# Memory.net
KiCad netlist of a schematic drawn in Altium Designer
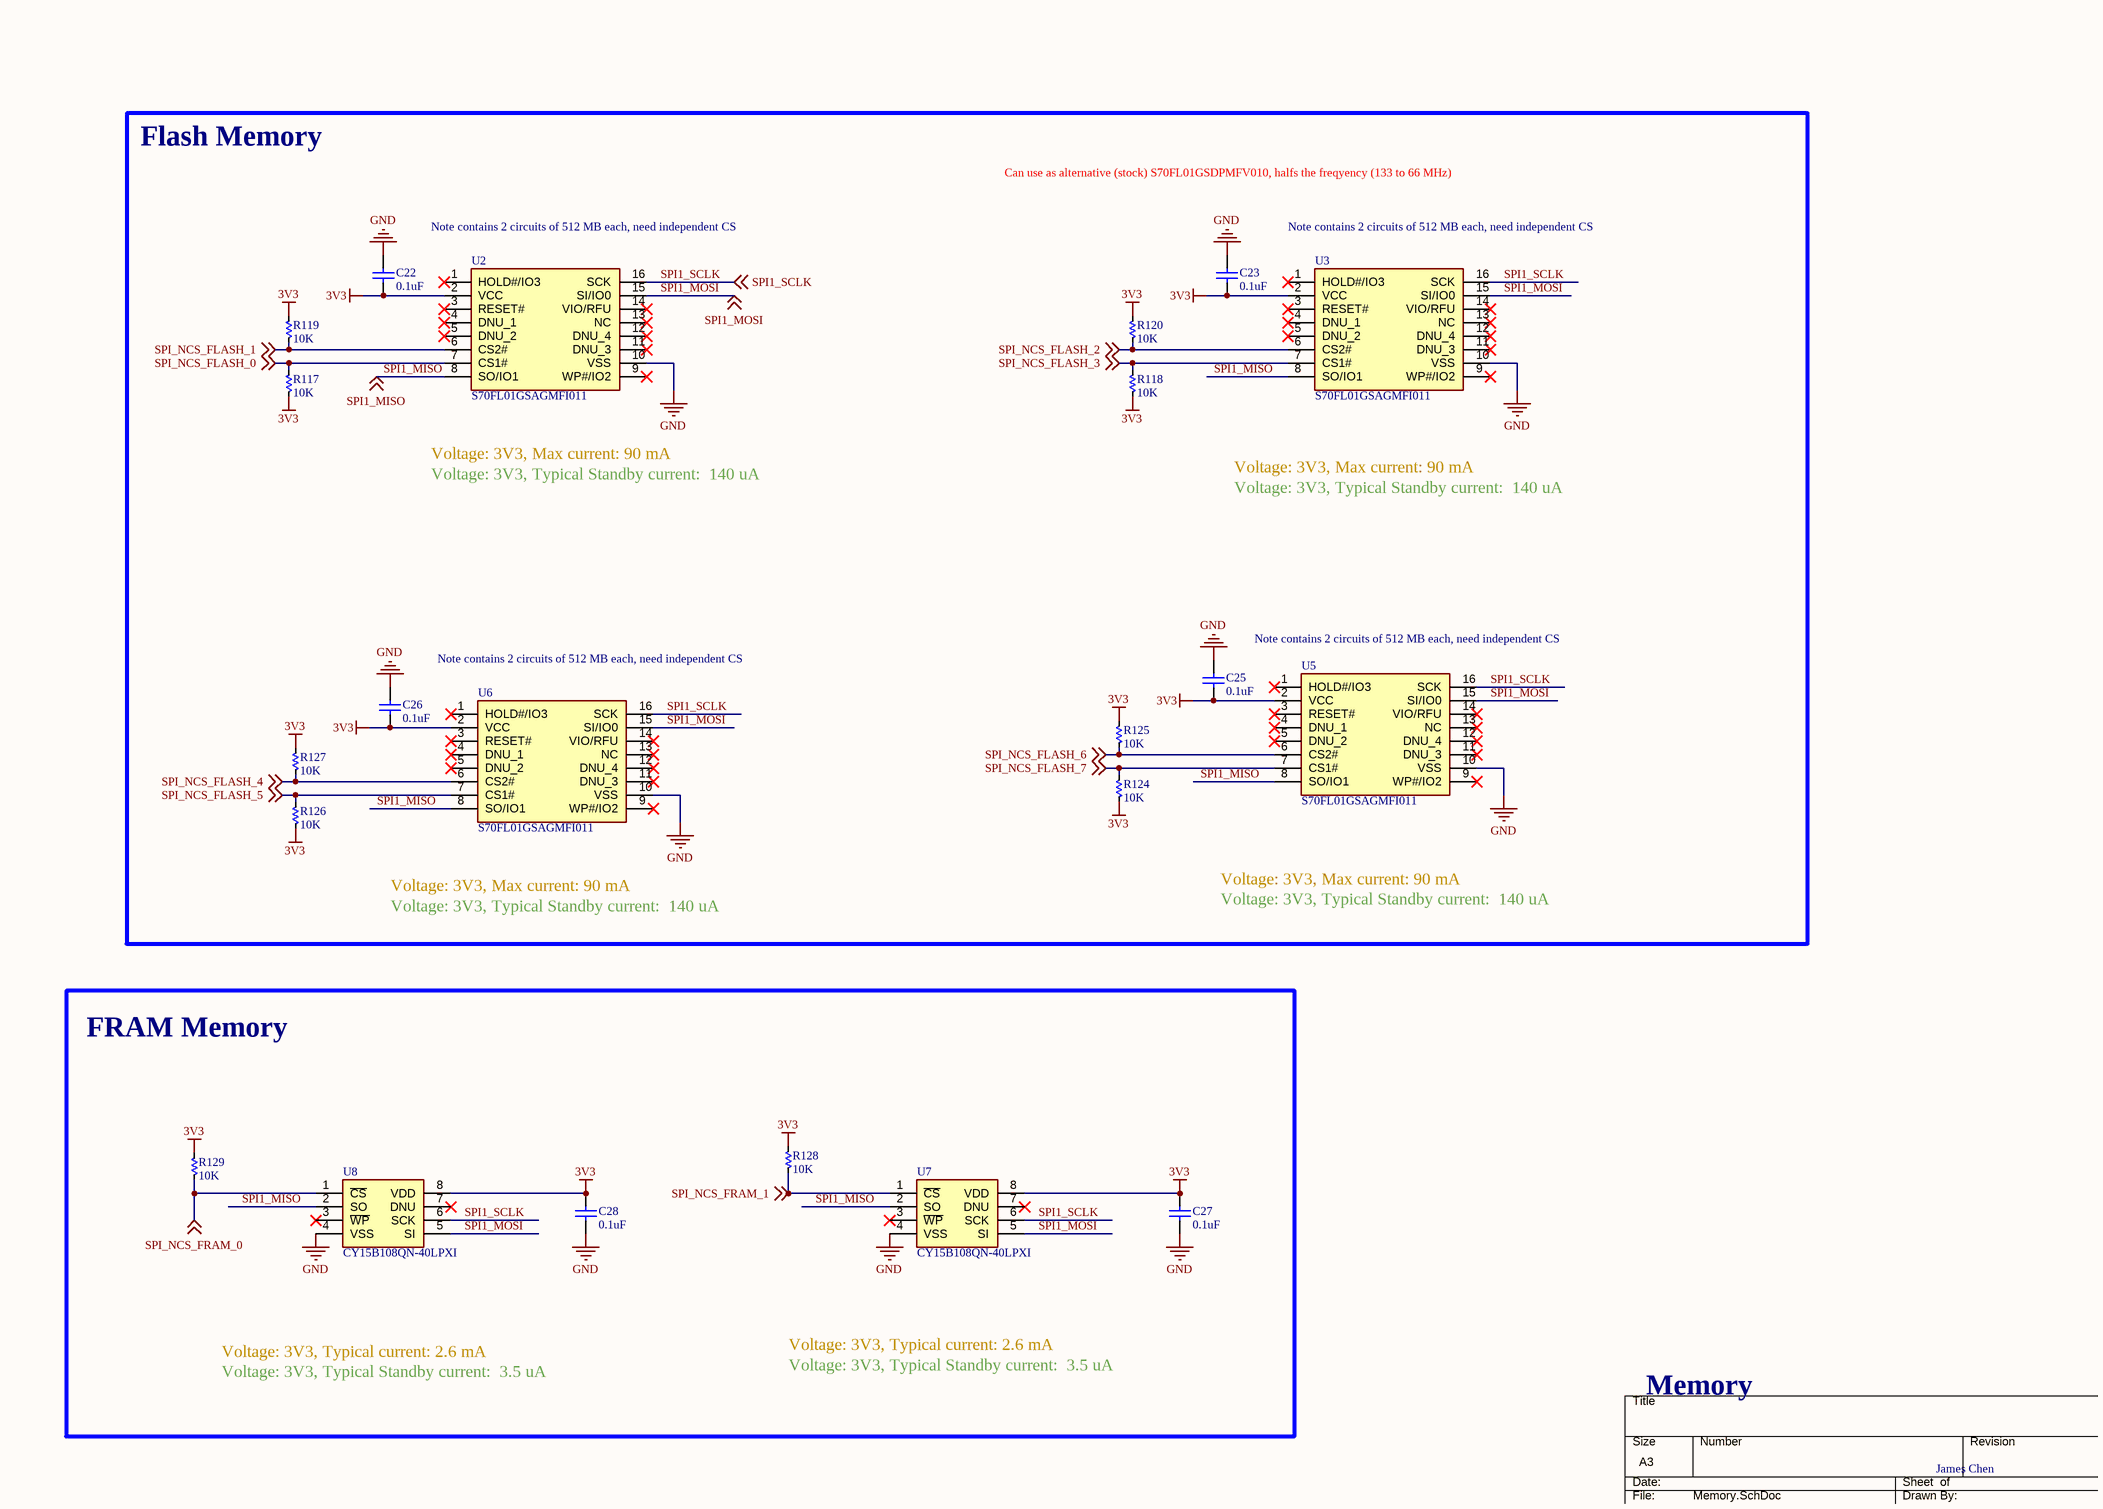
[diagram p0: Memory.SchDoc]

(export (version "E")
  (design (tool "Eeschema 10.0.6"))
  (components
    (comp (ref "C22")
      (value "0.1uF")
      (footprint "0603")
      (description "0.1 µF ±10% 25V Ceramic Capacitor X7R 0603 (1608 Metric)")
      (fields
        (field (name "DISTRIBUTOR PART #") "1276-1006-1-ND")
        (field (name "MANUFACTURER") "Samsung Electro-Mechanics")
      )
      (libsource (lib "OBC Development Board") (part "CC-104-K-25V-X7R-0603"))
    )
    (comp (ref "C23")
      (value "0.1uF")
      (footprint "0603")
      (description "0.1 µF ±10% 25V Ceramic Capacitor X7R 0603 (1608 Metric)")
      (fields
        (field (name "DISTRIBUTOR PART #") "1276-1006-1-ND")
        (field (name "MANUFACTURER") "Samsung Electro-Mechanics")
      )
      (libsource (lib "OBC Development Board") (part "CC-104-K-25V-X7R-0603"))
    )
    (comp (ref "C25")
      (value "0.1uF")
      (footprint "0603")
      (description "0.1 µF ±10% 25V Ceramic Capacitor X7R 0603 (1608 Metric)")
      (fields
        (field (name "DISTRIBUTOR PART #") "1276-1006-1-ND")
        (field (name "MANUFACTURER") "Samsung Electro-Mechanics")
      )
      (libsource (lib "OBC Development Board") (part "CC-104-K-25V-X7R-0603"))
    )
    (comp (ref "C26")
      (value "0.1uF")
      (footprint "0603")
      (description "0.1 µF ±10% 25V Ceramic Capacitor X7R 0603 (1608 Metric)")
      (fields
        (field (name "DISTRIBUTOR PART #") "1276-1006-1-ND")
        (field (name "MANUFACTURER") "Samsung Electro-Mechanics")
      )
      (libsource (lib "OBC Development Board") (part "CC-104-K-25V-X7R-0603"))
    )
    (comp (ref "C27")
      (value "0.1uF")
      (footprint "0603")
      (description "0.1 µF ±10% 25V Ceramic Capacitor X7R 0603 (1608 Metric)")
      (fields
        (field (name "DISTRIBUTOR PART #") "1276-1006-1-ND")
        (field (name "MANUFACTURER") "Samsung Electro-Mechanics")
      )
      (libsource (lib "OBC Development Board") (part "CC-104-K-25V-X7R-0603"))
    )
    (comp (ref "C28")
      (value "0.1uF")
      (footprint "0603")
      (description "0.1 µF ±10% 25V Ceramic Capacitor X7R 0603 (1608 Metric)")
      (fields
        (field (name "DISTRIBUTOR PART #") "1276-1006-1-ND")
        (field (name "MANUFACTURER") "Samsung Electro-Mechanics")
      )
      (libsource (lib "OBC Development Board") (part "CC-104-K-25V-X7R-0603"))
    )
    (comp (ref "R117")
      (value "10K")
      (footprint "0603")
      (description "10 kOhms ±0.1% 0.063W, 1/16W Chip Resistor 0603 (1608 Metric) - Thin Film")
      (fields
        (field (name "DISTRIBUTOR PART #") "A119886CT-ND")
        (field (name "MANUFACTURER") "TE Connectivity Passive Product")
      )
      (libsource (lib "OBC Development Board") (part "RT-10K0-F-1/16W-0603"))
    )
    (comp (ref "R118")
      (value "10K")
      (footprint "0603")
      (description "10 kOhms ±0.1% 0.063W, 1/16W Chip Resistor 0603 (1608 Metric) - Thin Film")
      (fields
        (field (name "DISTRIBUTOR PART #") "A119886CT-ND")
        (field (name "MANUFACTURER") "TE Connectivity Passive Product")
      )
      (libsource (lib "OBC Development Board") (part "RT-10K0-F-1/16W-0603"))
    )
    (comp (ref "R119")
      (value "10K")
      (footprint "0603")
      (description "10 kOhms ±0.1% 0.063W, 1/16W Chip Resistor 0603 (1608 Metric) - Thin Film")
      (fields
        (field (name "DISTRIBUTOR PART #") "A119886CT-ND")
        (field (name "MANUFACTURER") "TE Connectivity Passive Product")
      )
      (libsource (lib "OBC Development Board") (part "RT-10K0-F-1/16W-0603"))
    )
    (comp (ref "R120")
      (value "10K")
      (footprint "0603")
      (description "10 kOhms ±0.1% 0.063W, 1/16W Chip Resistor 0603 (1608 Metric) - Thin Film")
      (fields
        (field (name "DISTRIBUTOR PART #") "A119886CT-ND")
        (field (name "MANUFACTURER") "TE Connectivity Passive Product")
      )
      (libsource (lib "OBC Development Board") (part "RT-10K0-F-1/16W-0603"))
    )
    (comp (ref "R124")
      (value "10K")
      (footprint "0603")
      (description "10 kOhms ±0.1% 0.063W, 1/16W Chip Resistor 0603 (1608 Metric) - Thin Film")
      (fields
        (field (name "DISTRIBUTOR PART #") "A119886CT-ND")
        (field (name "MANUFACTURER") "TE Connectivity Passive Product")
      )
      (libsource (lib "OBC Development Board") (part "RT-10K0-F-1/16W-0603"))
    )
    (comp (ref "R125")
      (value "10K")
      (footprint "0603")
      (description "10 kOhms ±0.1% 0.063W, 1/16W Chip Resistor 0603 (1608 Metric) - Thin Film")
      (fields
        (field (name "DISTRIBUTOR PART #") "A119886CT-ND")
        (field (name "MANUFACTURER") "TE Connectivity Passive Product")
      )
      (libsource (lib "OBC Development Board") (part "RT-10K0-F-1/16W-0603"))
    )
    (comp (ref "R126")
      (value "10K")
      (footprint "0603")
      (description "10 kOhms ±0.1% 0.063W, 1/16W Chip Resistor 0603 (1608 Metric) - Thin Film")
      (fields
        (field (name "DISTRIBUTOR PART #") "A119886CT-ND")
        (field (name "MANUFACTURER") "TE Connectivity Passive Product")
      )
      (libsource (lib "OBC Development Board") (part "RT-10K0-F-1/16W-0603"))
    )
    (comp (ref "R127")
      (value "10K")
      (footprint "0603")
      (description "10 kOhms ±0.1% 0.063W, 1/16W Chip Resistor 0603 (1608 Metric) - Thin Film")
      (fields
        (field (name "DISTRIBUTOR PART #") "A119886CT-ND")
        (field (name "MANUFACTURER") "TE Connectivity Passive Product")
      )
      (libsource (lib "OBC Development Board") (part "RT-10K0-F-1/16W-0603"))
    )
    (comp (ref "R128")
      (value "10K")
      (footprint "0603")
      (description "10 kOhms ±0.1% 0.063W, 1/16W Chip Resistor 0603 (1608 Metric) - Thin Film")
      (fields
        (field (name "DISTRIBUTOR PART #") "A119886CT-ND")
        (field (name "MANUFACTURER") "TE Connectivity Passive Product")
      )
      (libsource (lib "OBC Development Board") (part "RT-10K0-F-1/16W-0603"))
    )
    (comp (ref "R129")
      (value "10K")
      (footprint "0603")
      (description "10 kOhms ±0.1% 0.063W, 1/16W Chip Resistor 0603 (1608 Metric) - Thin Film")
      (fields
        (field (name "DISTRIBUTOR PART #") "A119886CT-ND")
        (field (name "MANUFACTURER") "TE Connectivity Passive Product")
      )
      (libsource (lib "OBC Development Board") (part "RT-10K0-F-1/16W-0603"))
    )
    (comp (ref "U2")
      (value "S70FL01GSAGMFI011")
      (footprint "U-S70FL01GSAGMFI011")
      (description "IC FLASH 1GBIT SPI/QUAD 16SOIC")
      (fields
        (field (name "MANUFACTURER") "Cypress Semiconductor")
        (field (name "DISTRIBUTOR PART #") "1274-1092-ND")
      )
      (libsource (lib "OBC Development Board") (part "U-S70FL01GSAGMFI011"))
    )
    (comp (ref "U3")
      (value "S70FL01GSAGMFI011")
      (footprint "U-S70FL01GSAGMFI011")
      (description "IC FLASH 1GBIT SPI/QUAD 16SOIC")
      (fields
        (field (name "MANUFACTURER") "Cypress Semiconductor")
        (field (name "DISTRIBUTOR PART #") "1274-1092-ND")
      )
      (libsource (lib "OBC Development Board") (part "U-S70FL01GSAGMFI011"))
    )
    (comp (ref "U5")
      (value "S70FL01GSAGMFI011")
      (footprint "U-S70FL01GSAGMFI011")
      (description "IC FLASH 1GBIT SPI/QUAD 16SOIC")
      (fields
        (field (name "MANUFACTURER") "Cypress Semiconductor")
        (field (name "DISTRIBUTOR PART #") "1274-1092-ND")
      )
      (libsource (lib "OBC Development Board") (part "U-S70FL01GSAGMFI011"))
    )
    (comp (ref "U6")
      (value "S70FL01GSAGMFI011")
      (footprint "U-S70FL01GSAGMFI011")
      (description "IC FLASH 1GBIT SPI/QUAD 16SOIC")
      (fields
        (field (name "MANUFACTURER") "Cypress Semiconductor")
        (field (name "DISTRIBUTOR PART #") "1274-1092-ND")
      )
      (libsource (lib "OBC Development Board") (part "U-S70FL01GSAGMFI011"))
    )
    (comp (ref "U7")
      (value "CY15B108QN-40LPXI")
      (footprint "U-CY15B108QN-40LPXI")
      (description "IC FRAM 8MBIT SPI 40MHZ 8GQFN")
      (fields
        (field (name "MANUFACTURER") "Cypress Semiconductor")
        (field (name "DISTRIBUTOR PART #") "428-4723-ND")
      )
      (libsource (lib "OBC Development Board") (part "U-CY15B108QN-40LPXI"))
    )
    (comp (ref "U8")
      (value "CY15B108QN-40LPXI")
      (footprint "U-CY15B108QN-40LPXI")
      (description "IC FRAM 8MBIT SPI 40MHZ 8GQFN")
      (fields
        (field (name "MANUFACTURER") "Cypress Semiconductor")
        (field (name "DISTRIBUTOR PART #") "428-4723-ND")
      )
      (libsource (lib "OBC Development Board") (part "U-CY15B108QN-40LPXI"))
    )
  )
  (nets
    (net (code "1") (name "3V3") (class "Default")
      (node (ref "C22") (pin "1") (pinfunction "1_1") (pintype "passive"))
      (node (ref "C23") (pin "1") (pinfunction "1_1") (pintype "passive"))
      (node (ref "C25") (pin "1") (pinfunction "1_1") (pintype "passive"))
      (node (ref "C26") (pin "1") (pinfunction "1_1") (pintype "passive"))
      (node (ref "C27") (pin "1") (pinfunction "1_1") (pintype "passive"))
      (node (ref "C28") (pin "1") (pinfunction "1_1") (pintype "passive"))
      (node (ref "R117") (pin "1") (pintype "passive"))
      (node (ref "R118") (pin "1") (pintype "passive"))
      (node (ref "R119") (pin "1") (pintype "passive"))
      (node (ref "R120") (pin "2") (pintype "passive"))
      (node (ref "R124") (pin "1") (pintype "passive"))
      (node (ref "R125") (pin "2") (pintype "passive"))
      (node (ref "R126") (pin "1") (pintype "passive"))
      (node (ref "R127") (pin "2") (pintype "passive"))
      (node (ref "R128") (pin "1") (pintype "passive"))
      (node (ref "R129") (pin "1") (pintype "passive"))
      (node (ref "U2") (pin "2") (pinfunction "VCC_2") (pintype "passive"))
      (node (ref "U3") (pin "2") (pinfunction "VCC_2") (pintype "passive"))
      (node (ref "U5") (pin "2") (pinfunction "VCC_2") (pintype "passive"))
      (node (ref "U6") (pin "2") (pinfunction "VCC_2") (pintype "passive"))
      (node (ref "U7") (pin "8") (pinfunction "VDD_8") (pintype "passive"))
      (node (ref "U8") (pin "8") (pinfunction "VDD_8") (pintype "passive"))
    )
    (net (code "2") (name "GND") (class "Default")
      (node (ref "C22") (pin "2") (pinfunction "2_2") (pintype "passive"))
      (node (ref "C23") (pin "2") (pinfunction "2_2") (pintype "passive"))
      (node (ref "C25") (pin "2") (pinfunction "2_2") (pintype "passive"))
      (node (ref "C26") (pin "2") (pinfunction "2_2") (pintype "passive"))
      (node (ref "C27") (pin "2") (pinfunction "2_2") (pintype "passive"))
      (node (ref "C28") (pin "2") (pinfunction "2_2") (pintype "passive"))
      (node (ref "U2") (pin "10") (pinfunction "VSS_10") (pintype "passive"))
      (node (ref "U3") (pin "10") (pinfunction "VSS_10") (pintype "passive"))
      (node (ref "U5") (pin "10") (pinfunction "VSS_10") (pintype "passive"))
      (node (ref "U6") (pin "10") (pinfunction "VSS_10") (pintype "passive"))
      (node (ref "U7") (pin "4") (pinfunction "VSS_4") (pintype "passive"))
      (node (ref "U8") (pin "4") (pinfunction "VSS_4") (pintype "passive"))
    )
    (net (code "3") (name "SPI1_MISO") (class "Default")
      (node (ref "U2") (pin "8") (pinfunction "SO/IO1_8") (pintype "passive"))
      (node (ref "U3") (pin "8") (pinfunction "SO/IO1_8") (pintype "passive"))
      (node (ref "U5") (pin "8") (pinfunction "SO/IO1_8") (pintype "passive"))
      (node (ref "U6") (pin "8") (pinfunction "SO/IO1_8") (pintype "passive"))
      (node (ref "U7") (pin "2") (pinfunction "SO_2") (pintype "passive"))
      (node (ref "U8") (pin "2") (pinfunction "SO_2") (pintype "passive"))
    )
    (net (code "4") (name "SPI1_MOSI") (class "Default")
      (node (ref "U2") (pin "15") (pinfunction "SI/IO0_15") (pintype "passive"))
      (node (ref "U3") (pin "15") (pinfunction "SI/IO0_15") (pintype "passive"))
      (node (ref "U5") (pin "15") (pinfunction "SI/IO0_15") (pintype "passive"))
      (node (ref "U6") (pin "15") (pinfunction "SI/IO0_15") (pintype "passive"))
      (node (ref "U7") (pin "5") (pinfunction "SI_5") (pintype "passive"))
      (node (ref "U8") (pin "5") (pinfunction "SI_5") (pintype "passive"))
    )
    (net (code "5") (name "SPI1_SCLK") (class "Default")
      (node (ref "U2") (pin "16") (pinfunction "SCK_16") (pintype "passive"))
      (node (ref "U3") (pin "16") (pinfunction "SCK_16") (pintype "passive"))
      (node (ref "U5") (pin "16") (pinfunction "SCK_16") (pintype "passive"))
      (node (ref "U6") (pin "16") (pinfunction "SCK_16") (pintype "passive"))
      (node (ref "U7") (pin "6") (pinfunction "SCK_6") (pintype "passive"))
      (node (ref "U8") (pin "6") (pinfunction "SCK_6") (pintype "passive"))
    )
    (net (code "6") (name "SPI_NCS_FLASH_0") (class "Default")
      (node (ref "R117") (pin "2") (pintype "passive"))
      (node (ref "U2") (pin "7") (pinfunction "CS1#_7") (pintype "passive"))
    )
    (net (code "7") (name "SPI_NCS_FLASH_1") (class "Default")
      (node (ref "R119") (pin "2") (pintype "passive"))
      (node (ref "U2") (pin "6") (pinfunction "CS2#_6") (pintype "passive"))
    )
    (net (code "8") (name "SPI_NCS_FLASH_2") (class "Default")
      (node (ref "R120") (pin "1") (pintype "passive"))
      (node (ref "U3") (pin "6") (pinfunction "CS2#_6") (pintype "passive"))
    )
    (net (code "9") (name "SPI_NCS_FLASH_3") (class "Default")
      (node (ref "R118") (pin "2") (pintype "passive"))
      (node (ref "U3") (pin "7") (pinfunction "CS1#_7") (pintype "passive"))
    )
    (net (code "10") (name "SPI_NCS_FLASH_4") (class "Default")
      (node (ref "R127") (pin "1") (pintype "passive"))
      (node (ref "U6") (pin "6") (pinfunction "CS2#_6") (pintype "passive"))
    )
    (net (code "11") (name "SPI_NCS_FLASH_5") (class "Default")
      (node (ref "R126") (pin "2") (pintype "passive"))
      (node (ref "U6") (pin "7") (pinfunction "CS1#_7") (pintype "passive"))
    )
    (net (code "12") (name "SPI_NCS_FLASH_6") (class "Default")
      (node (ref "R125") (pin "1") (pintype "passive"))
      (node (ref "U5") (pin "6") (pinfunction "CS2#_6") (pintype "passive"))
    )
    (net (code "13") (name "SPI_NCS_FLASH_7") (class "Default")
      (node (ref "R124") (pin "2") (pintype "passive"))
      (node (ref "U5") (pin "7") (pinfunction "CS1#_7") (pintype "passive"))
    )
    (net (code "14") (name "SPI_NCS_FRAM_0") (class "Default")
      (node (ref "R129") (pin "2") (pintype "passive"))
      (node (ref "U8") (pin "1") (pinfunction "~{CS}_1") (pintype "passive"))
    )
    (net (code "15") (name "SPI_NCS_FRAM_1") (class "Default")
      (node (ref "R128") (pin "2") (pintype "passive"))
      (node (ref "U7") (pin "1") (pinfunction "~{CS}_1") (pintype "passive"))
    )
    (net (code "16") (name "unconnected-(U2-DNU_1-Pad4)") (class "Default")
      (node (ref "U2") (pin "4") (pinfunction "DNU_1_4") (pintype "passive+no_connect"))
    )
    (net (code "17") (name "unconnected-(U2-DNU_2-Pad5)") (class "Default")
      (node (ref "U2") (pin "5") (pinfunction "DNU_2_5") (pintype "passive+no_connect"))
    )
    (net (code "18") (name "unconnected-(U2-DNU_3-Pad11)") (class "Default")
      (node (ref "U2") (pin "11") (pinfunction "DNU_3_11") (pintype "passive+no_connect"))
    )
    (net (code "19") (name "unconnected-(U2-DNU_4-Pad12)") (class "Default")
      (node (ref "U2") (pin "12") (pinfunction "DNU_4_12") (pintype "passive+no_connect"))
    )
    (net (code "20") (name "unconnected-(U2-HOLD#{slash}IO3-Pad1)") (class "Default")
      (node (ref "U2") (pin "1") (pinfunction "HOLD#/IO3_1") (pintype "passive+no_connect"))
    )
    (net (code "21") (name "unconnected-(U2-NC-Pad13)") (class "Default")
      (node (ref "U2") (pin "13") (pinfunction "NC_13") (pintype "passive+no_connect"))
    )
    (net (code "22") (name "unconnected-(U2-RESET#-Pad3)") (class "Default")
      (node (ref "U2") (pin "3") (pinfunction "RESET#_3") (pintype "passive+no_connect"))
    )
    (net (code "23") (name "unconnected-(U2-VIO{slash}RFU-Pad14)") (class "Default")
      (node (ref "U2") (pin "14") (pinfunction "VIO/RFU_14") (pintype "passive+no_connect"))
    )
    (net (code "24") (name "unconnected-(U2-WP#{slash}IO2-Pad9)") (class "Default")
      (node (ref "U2") (pin "9") (pinfunction "WP#/IO2_9") (pintype "passive+no_connect"))
    )
    (net (code "25") (name "unconnected-(U3-DNU_1-Pad4)") (class "Default")
      (node (ref "U3") (pin "4") (pinfunction "DNU_1_4") (pintype "passive+no_connect"))
    )
    (net (code "26") (name "unconnected-(U3-DNU_2-Pad5)") (class "Default")
      (node (ref "U3") (pin "5") (pinfunction "DNU_2_5") (pintype "passive+no_connect"))
    )
    (net (code "27") (name "unconnected-(U3-DNU_3-Pad11)") (class "Default")
      (node (ref "U3") (pin "11") (pinfunction "DNU_3_11") (pintype "passive+no_connect"))
    )
    (net (code "28") (name "unconnected-(U3-DNU_4-Pad12)") (class "Default")
      (node (ref "U3") (pin "12") (pinfunction "DNU_4_12") (pintype "passive+no_connect"))
    )
    (net (code "29") (name "unconnected-(U3-HOLD#{slash}IO3-Pad1)") (class "Default")
      (node (ref "U3") (pin "1") (pinfunction "HOLD#/IO3_1") (pintype "passive+no_connect"))
    )
    (net (code "30") (name "unconnected-(U3-NC-Pad13)") (class "Default")
      (node (ref "U3") (pin "13") (pinfunction "NC_13") (pintype "passive+no_connect"))
    )
    (net (code "31") (name "unconnected-(U3-RESET#-Pad3)") (class "Default")
      (node (ref "U3") (pin "3") (pinfunction "RESET#_3") (pintype "passive+no_connect"))
    )
    (net (code "32") (name "unconnected-(U3-VIO{slash}RFU-Pad14)") (class "Default")
      (node (ref "U3") (pin "14") (pinfunction "VIO/RFU_14") (pintype "passive+no_connect"))
    )
    (net (code "33") (name "unconnected-(U3-WP#{slash}IO2-Pad9)") (class "Default")
      (node (ref "U3") (pin "9") (pinfunction "WP#/IO2_9") (pintype "passive+no_connect"))
    )
    (net (code "34") (name "unconnected-(U5-DNU_1-Pad4)") (class "Default")
      (node (ref "U5") (pin "4") (pinfunction "DNU_1_4") (pintype "passive+no_connect"))
    )
    (net (code "35") (name "unconnected-(U5-DNU_2-Pad5)") (class "Default")
      (node (ref "U5") (pin "5") (pinfunction "DNU_2_5") (pintype "passive+no_connect"))
    )
    (net (code "36") (name "unconnected-(U5-DNU_3-Pad11)") (class "Default")
      (node (ref "U5") (pin "11") (pinfunction "DNU_3_11") (pintype "passive+no_connect"))
    )
    (net (code "37") (name "unconnected-(U5-DNU_4-Pad12)") (class "Default")
      (node (ref "U5") (pin "12") (pinfunction "DNU_4_12") (pintype "passive+no_connect"))
    )
    (net (code "38") (name "unconnected-(U5-HOLD#{slash}IO3-Pad1)") (class "Default")
      (node (ref "U5") (pin "1") (pinfunction "HOLD#/IO3_1") (pintype "passive+no_connect"))
    )
    (net (code "39") (name "unconnected-(U5-NC-Pad13)") (class "Default")
      (node (ref "U5") (pin "13") (pinfunction "NC_13") (pintype "passive+no_connect"))
    )
    (net (code "40") (name "unconnected-(U5-RESET#-Pad3)") (class "Default")
      (node (ref "U5") (pin "3") (pinfunction "RESET#_3") (pintype "passive+no_connect"))
    )
    (net (code "41") (name "unconnected-(U5-VIO{slash}RFU-Pad14)") (class "Default")
      (node (ref "U5") (pin "14") (pinfunction "VIO/RFU_14") (pintype "passive+no_connect"))
    )
    (net (code "42") (name "unconnected-(U5-WP#{slash}IO2-Pad9)") (class "Default")
      (node (ref "U5") (pin "9") (pinfunction "WP#/IO2_9") (pintype "passive+no_connect"))
    )
    (net (code "43") (name "unconnected-(U6-DNU_1-Pad4)") (class "Default")
      (node (ref "U6") (pin "4") (pinfunction "DNU_1_4") (pintype "passive+no_connect"))
    )
    (net (code "44") (name "unconnected-(U6-DNU_2-Pad5)") (class "Default")
      (node (ref "U6") (pin "5") (pinfunction "DNU_2_5") (pintype "passive+no_connect"))
    )
    (net (code "45") (name "unconnected-(U6-DNU_3-Pad11)") (class "Default")
      (node (ref "U6") (pin "11") (pinfunction "DNU_3_11") (pintype "passive+no_connect"))
    )
    (net (code "46") (name "unconnected-(U6-DNU_4-Pad12)") (class "Default")
      (node (ref "U6") (pin "12") (pinfunction "DNU_4_12") (pintype "passive+no_connect"))
    )
    (net (code "47") (name "unconnected-(U6-HOLD#{slash}IO3-Pad1)") (class "Default")
      (node (ref "U6") (pin "1") (pinfunction "HOLD#/IO3_1") (pintype "passive+no_connect"))
    )
    (net (code "48") (name "unconnected-(U6-NC-Pad13)") (class "Default")
      (node (ref "U6") (pin "13") (pinfunction "NC_13") (pintype "passive+no_connect"))
    )
    (net (code "49") (name "unconnected-(U6-RESET#-Pad3)") (class "Default")
      (node (ref "U6") (pin "3") (pinfunction "RESET#_3") (pintype "passive+no_connect"))
    )
    (net (code "50") (name "unconnected-(U6-VIO{slash}RFU-Pad14)") (class "Default")
      (node (ref "U6") (pin "14") (pinfunction "VIO/RFU_14") (pintype "passive+no_connect"))
    )
    (net (code "51") (name "unconnected-(U6-WP#{slash}IO2-Pad9)") (class "Default")
      (node (ref "U6") (pin "9") (pinfunction "WP#/IO2_9") (pintype "passive+no_connect"))
    )
    (net (code "52") (name "unconnected-(U7-DNU-Pad7)") (class "Default")
      (node (ref "U7") (pin "7") (pinfunction "DNU_7") (pintype "passive+no_connect"))
    )
    (net (code "53") (name "unconnected-(U7-~{WP}-Pad3)") (class "Default")
      (node (ref "U7") (pin "3") (pinfunction "~{WP}_3") (pintype "passive+no_connect"))
    )
    (net (code "54") (name "unconnected-(U8-DNU-Pad7)") (class "Default")
      (node (ref "U8") (pin "7") (pinfunction "DNU_7") (pintype "passive+no_connect"))
    )
    (net (code "55") (name "unconnected-(U8-~{WP}-Pad3)") (class "Default")
      (node (ref "U8") (pin "3") (pinfunction "~{WP}_3") (pintype "passive+no_connect"))
    )
  )
)
